# adapter.net
KiCad netlist of a schematic drawn in EAGLE
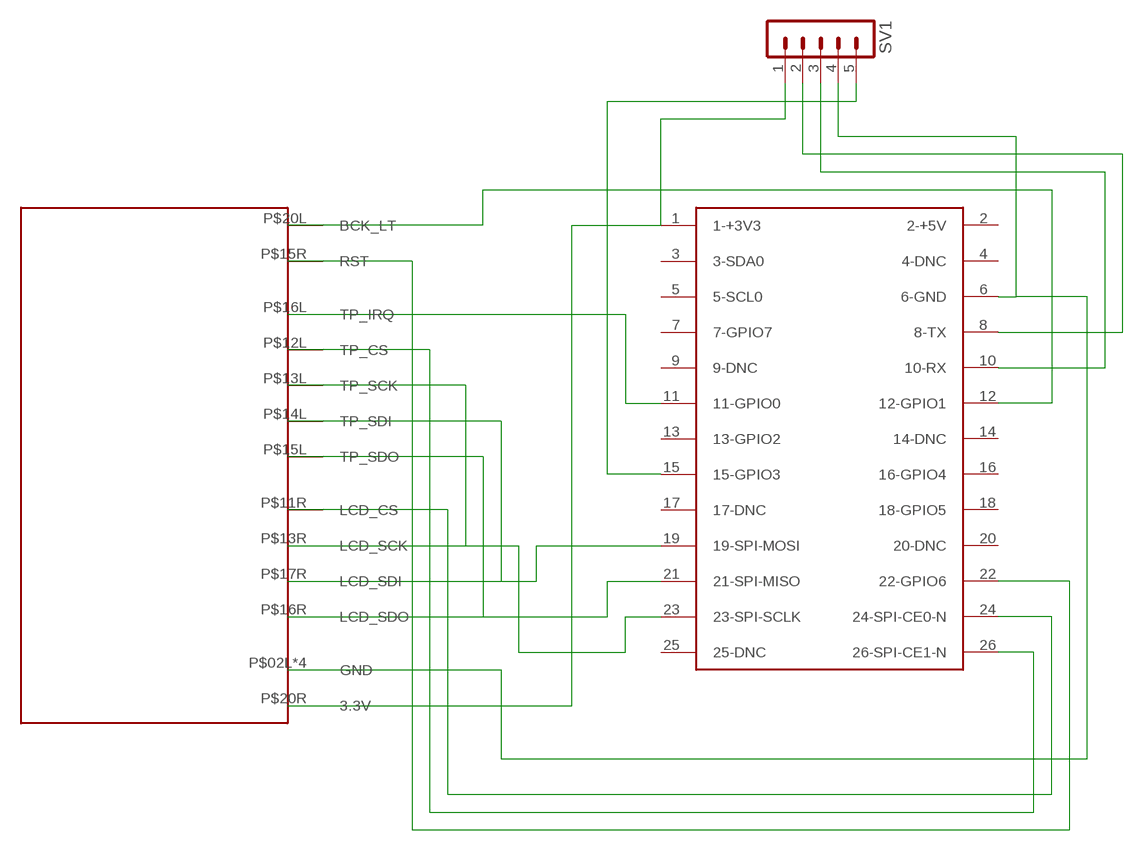
[diagram p0: schematic, sheet 1]

(export (version "E")
  (design (tool "Eeschema 10.0.6"))
  (components
    (comp (ref "SV1")
      (value "MA05-1")
      (footprint "eagle-import:MA05-1")
      (libsource (lib "eagle-import") (part "MA05-1"))
    )
    (comp (ref "U$1")
      (value "HY28BSTD")
      (footprint "eagle-import:HY28B")
      (libsource (lib "eagle-import") (part "HY28BSTD"))
    )
    (comp (ref "U$2")
      (value "RASPBERRY-PI")
      (footprint "eagle-import:RASPBERRY-PI")
      (libsource (lib "eagle-import") (part "RASPBERRY-PI"))
    )
  )
  (nets
    (net (code "1") (name "Net-(U$1-3.3V)") (class "Default")
      (node (ref "SV1") (pin "1") (pinfunction "1_1") (pintype "passive"))
      (node (ref "U$1") (pin "P$20R") (pinfunction "3.3V_P$20R") (pintype "bidirectional"))
      (node (ref "U$2") (pin "1") (pinfunction "1-+3V3_1") (pintype "bidirectional"))
    )
    (net (code "2") (name "Net-(U$1-BCK_LT)") (class "Default")
      (node (ref "U$1") (pin "P$20L") (pinfunction "BCK_LT_P$20L") (pintype "bidirectional"))
      (node (ref "U$2") (pin "12") (pinfunction "12-GPIO1_12") (pintype "bidirectional"))
    )
    (net (code "3") (name "Net-(U$1-LCD_CS)") (class "Default")
      (node (ref "U$1") (pin "P$11R") (pinfunction "LCD_CS_P$11R") (pintype "bidirectional"))
      (node (ref "U$2") (pin "24") (pinfunction "24-SPI-CE0-N_24") (pintype "bidirectional"))
    )
    (net (code "4") (name "Net-(U$1-LCD_SCK)") (class "Default")
      (node (ref "U$1") (pin "P$13L") (pinfunction "TP_SCK_P$13L") (pintype "bidirectional"))
      (node (ref "U$1") (pin "P$13R") (pinfunction "LCD_SCK_P$13R") (pintype "bidirectional"))
      (node (ref "U$2") (pin "23") (pinfunction "23-SPI-SCLK_23") (pintype "bidirectional"))
    )
    (net (code "5") (name "Net-(U$1-LCD_SDI)") (class "Default")
      (node (ref "U$1") (pin "P$14L") (pinfunction "TP_SDI_P$14L") (pintype "bidirectional"))
      (node (ref "U$1") (pin "P$17R") (pinfunction "LCD_SDI_P$17R") (pintype "bidirectional"))
      (node (ref "U$2") (pin "19") (pinfunction "19-SPI-MOSI_19") (pintype "bidirectional"))
    )
    (net (code "6") (name "Net-(U$1-LCD_SDO)") (class "Default")
      (node (ref "U$1") (pin "P$15L") (pinfunction "TP_SDO_P$15L") (pintype "bidirectional"))
      (node (ref "U$1") (pin "P$16R") (pinfunction "LCD_SDO_P$16R") (pintype "bidirectional"))
      (node (ref "U$2") (pin "21") (pinfunction "21-SPI-MISO_21") (pintype "bidirectional"))
    )
    (net (code "7") (name "Net-(U$1-RST)") (class "Default")
      (node (ref "U$1") (pin "P$15R") (pinfunction "RST_P$15R") (pintype "bidirectional"))
      (node (ref "U$2") (pin "22") (pinfunction "22-GPIO6_22") (pintype "bidirectional"))
    )
    (net (code "8") (name "Net-(U$1-TP_CS)") (class "Default")
      (node (ref "U$1") (pin "P$12L") (pinfunction "TP_CS_P$12L") (pintype "bidirectional"))
      (node (ref "U$2") (pin "26") (pinfunction "26-SPI-CE1-N_26") (pintype "bidirectional"))
    )
    (net (code "9") (name "Net-(U$1-TP_IRQ)") (class "Default")
      (node (ref "U$1") (pin "P$16L") (pinfunction "TP_IRQ_P$16L") (pintype "bidirectional"))
      (node (ref "U$2") (pin "11") (pinfunction "11-GPIO0_11") (pintype "bidirectional"))
    )
    (net (code "10") (name "Net-(U$2-6-GND)") (class "Default")
      (node (ref "SV1") (pin "4") (pinfunction "4_4") (pintype "passive"))
      (node (ref "U$1") (pin "P$02L") (pinfunction "GND_P$02L") (pintype "bidirectional"))
      (node (ref "U$1") (pin "P$02R") (pinfunction "GND_P$02R") (pintype "bidirectional"))
      (node (ref "U$1") (pin "P$19L") (pinfunction "GND_P$19L") (pintype "bidirectional"))
      (node (ref "U$1") (pin "P$19R") (pinfunction "GND_P$19R") (pintype "bidirectional"))
      (node (ref "U$2") (pin "6") (pinfunction "6-GND_6") (pintype "bidirectional"))
    )
    (net (code "11") (name "Net-(U$2-8-TX)") (class "Default")
      (node (ref "SV1") (pin "2") (pinfunction "2_2") (pintype "passive"))
      (node (ref "U$2") (pin "8") (pinfunction "8-TX_8") (pintype "bidirectional"))
    )
    (net (code "12") (name "Net-(U$2-10-RX)") (class "Default")
      (node (ref "SV1") (pin "3") (pinfunction "3_3") (pintype "passive"))
      (node (ref "U$2") (pin "10") (pinfunction "10-RX_10") (pintype "bidirectional"))
    )
    (net (code "13") (name "Net-(U$2-15-GPIO3)") (class "Default")
      (node (ref "SV1") (pin "5") (pinfunction "5_5") (pintype "passive"))
      (node (ref "U$2") (pin "15") (pinfunction "15-GPIO3_15") (pintype "bidirectional"))
    )
    (net (code "14") (name "unconnected-(U$2-2-+5V-Pad2)") (class "Default")
      (node (ref "U$2") (pin "2") (pinfunction "2-+5V_2") (pintype "bidirectional"))
    )
    (net (code "15") (name "unconnected-(U$2-3-SDA0-Pad3)") (class "Default")
      (node (ref "U$2") (pin "3") (pinfunction "3-SDA0_3") (pintype "bidirectional"))
    )
    (net (code "16") (name "unconnected-(U$2-4-DNC-Pad4)") (class "Default")
      (node (ref "U$2") (pin "4") (pinfunction "4-DNC_4") (pintype "bidirectional"))
    )
    (net (code "17") (name "unconnected-(U$2-5-SCL0-Pad5)") (class "Default")
      (node (ref "U$2") (pin "5") (pinfunction "5-SCL0_5") (pintype "bidirectional"))
    )
    (net (code "18") (name "unconnected-(U$2-7-GPIO7-Pad7)") (class "Default")
      (node (ref "U$2") (pin "7") (pinfunction "7-GPIO7_7") (pintype "bidirectional"))
    )
    (net (code "19") (name "unconnected-(U$2-9-DNC-Pad9)") (class "Default")
      (node (ref "U$2") (pin "9") (pinfunction "9-DNC_9") (pintype "bidirectional"))
    )
    (net (code "20") (name "unconnected-(U$2-13-GPIO2-Pad13)") (class "Default")
      (node (ref "U$2") (pin "13") (pinfunction "13-GPIO2_13") (pintype "bidirectional"))
    )
    (net (code "21") (name "unconnected-(U$2-14-DNC-Pad14)") (class "Default")
      (node (ref "U$2") (pin "14") (pinfunction "14-DNC_14") (pintype "bidirectional"))
    )
    (net (code "22") (name "unconnected-(U$2-16-GPIO4-Pad16)") (class "Default")
      (node (ref "U$2") (pin "16") (pinfunction "16-GPIO4_16") (pintype "bidirectional"))
    )
    (net (code "23") (name "unconnected-(U$2-17-DNC-Pad17)") (class "Default")
      (node (ref "U$2") (pin "17") (pinfunction "17-DNC_17") (pintype "bidirectional"))
    )
    (net (code "24") (name "unconnected-(U$2-18-GPIO5-Pad18)") (class "Default")
      (node (ref "U$2") (pin "18") (pinfunction "18-GPIO5_18") (pintype "bidirectional"))
    )
    (net (code "25") (name "unconnected-(U$2-20-DNC-Pad20)") (class "Default")
      (node (ref "U$2") (pin "20") (pinfunction "20-DNC_20") (pintype "bidirectional"))
    )
    (net (code "26") (name "unconnected-(U$2-25-DNC-Pad25)") (class "Default")
      (node (ref "U$2") (pin "25") (pinfunction "25-DNC_25") (pintype "bidirectional"))
    )
  )
)
